# leddriverv3.net
KiCad netlist of a schematic drawn in EAGLE
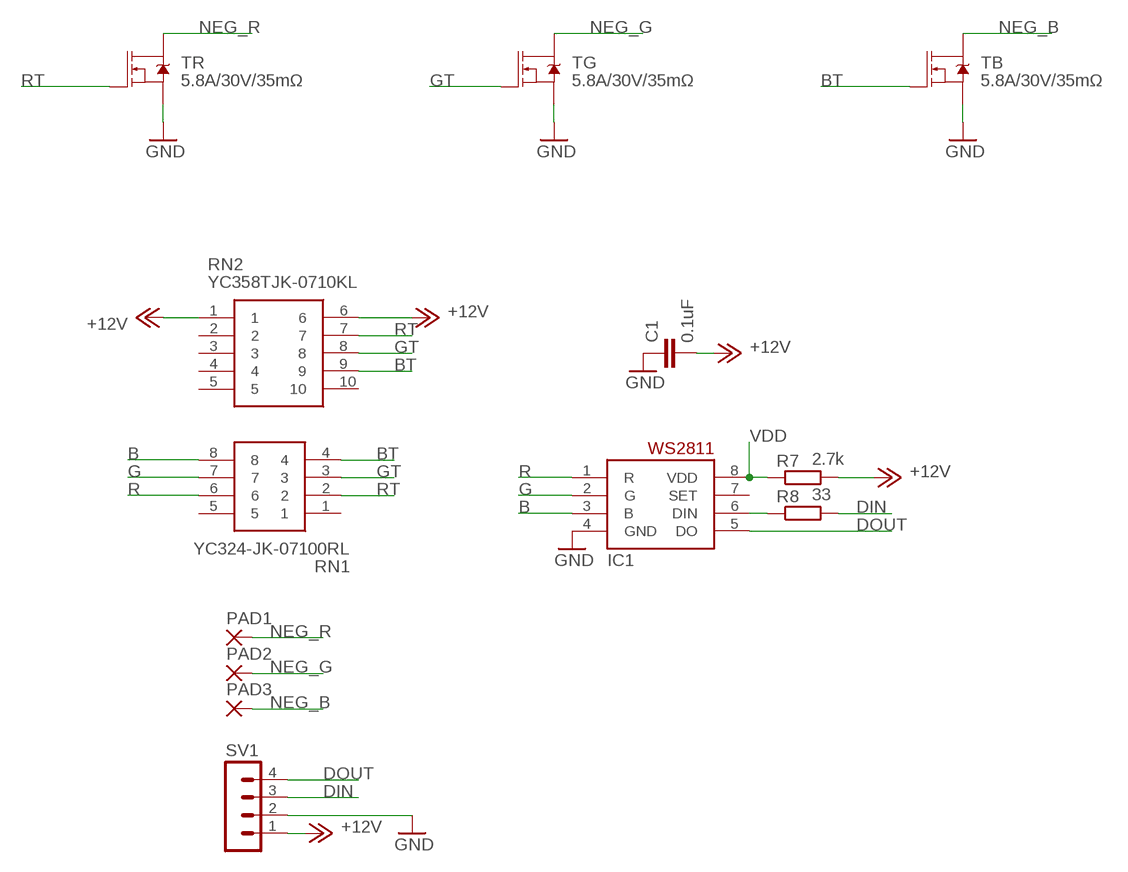
[diagram p0: schematic, sheet 1]

(export (version "E")
  (design (tool "Eeschema 10.0.6"))
  (components
    (comp (ref "C1")
      (value "0.1uF")
      (footprint "eagle-import:C1206")
      (libsource (lib "eagle-import") (part "C-EUC1206"))
    )
    (comp (ref "IC1")
      (value "WS2811-SOP8")
      (footprint "eagle-import:SO08-SKINNYPADS")
      (libsource (lib "eagle-import") (part "WS2811-SOP8"))
    )
    (comp (ref "PAD1")
      (value "3,81/1,4")
      (footprint "eagle-import:3,81_1,4")
      (libsource (lib "eagle-import") (part "3,81/1,4"))
    )
    (comp (ref "PAD2")
      (value "3,81/1,4")
      (footprint "eagle-import:3,81_1,4")
      (libsource (lib "eagle-import") (part "3,81/1,4"))
    )
    (comp (ref "PAD3")
      (value "3,81/1,4")
      (footprint "eagle-import:3,81_1,4")
      (libsource (lib "eagle-import") (part "3,81/1,4"))
    )
    (comp (ref "R7")
      (value "2.7k")
      (footprint "eagle-import:R0805")
      (libsource (lib "eagle-import") (part "R-EU_R0805"))
    )
    (comp (ref "R8")
      (value "33")
      (footprint "eagle-import:R0805")
      (libsource (lib "eagle-import") (part "R-EU_R0805"))
    )
    (comp (ref "RN1")
      (value "YC324-JK-07100RL")
      (footprint "eagle-import:YC324JK07100RL")
      (fields (field (name "MOUSER_PART_NUMBER") "603-YC324-JK-07100RL"))
      (libsource (lib "eagle-import") (part "YC324-JK-07100RL"))
    )
    (comp (ref "RN2")
      (value "YC358TJK-0710KL")
      (footprint "eagle-import:YC358T")
      (fields (field (name "MOUSER_PART_NUMBER") "603-YC358TJK-0710KL"))
      (libsource (lib "eagle-import") (part "YC358TJK-0710KL"))
    )
    (comp (ref "SV1")
      (value "MA04-1")
      (footprint "eagle-import:MA04-1")
      (libsource (lib "eagle-import") (part "MA04-1"))
    )
    (comp (ref "TB")
      (value "5.8A/30V/35mΩ")
      (footprint "eagle-import:SOT23-3")
      (libsource (lib "eagle-import") (part "MOSFET-NCH-AO3404A"))
    )
    (comp (ref "TG")
      (value "5.8A/30V/35mΩ")
      (footprint "eagle-import:SOT23-3")
      (libsource (lib "eagle-import") (part "MOSFET-NCH-AO3404A"))
    )
    (comp (ref "TR")
      (value "5.8A/30V/35mΩ")
      (footprint "eagle-import:SOT23-3")
      (libsource (lib "eagle-import") (part "MOSFET-NCH-AO3404A"))
    )
  )
  (nets
    (net (code "1") (name "+12V") (class "Default")
      (node (ref "C1") (pin "2") (pinfunction "2_2") (pintype "passive"))
      (node (ref "R7") (pin "2") (pinfunction "2_2") (pintype "passive"))
      (node (ref "RN2") (pin "1") (pinfunction "1_1") (pintype "bidirectional"))
      (node (ref "RN2") (pin "6") (pinfunction "6_6") (pintype "bidirectional"))
      (node (ref "SV1") (pin "1") (pinfunction "1_1") (pintype "passive"))
    )
    (net (code "2") (name "/B") (class "Default")
      (node (ref "IC1") (pin "3") (pinfunction "B_3") (pintype "open_collector"))
      (node (ref "RN1") (pin "8") (pinfunction "8_8") (pintype "bidirectional"))
    )
    (net (code "3") (name "/BT") (class "Default")
      (node (ref "RN1") (pin "4") (pinfunction "4_4") (pintype "bidirectional"))
      (node (ref "RN2") (pin "9") (pinfunction "9_9") (pintype "bidirectional"))
      (node (ref "TB") (pin "1") (pinfunction "G_1") (pintype "bidirectional"))
    )
    (net (code "4") (name "/DIN") (class "Default")
      (node (ref "R8") (pin "2") (pinfunction "2_2") (pintype "passive"))
      (node (ref "SV1") (pin "3") (pinfunction "3_3") (pintype "passive"))
    )
    (net (code "5") (name "/DOUT") (class "Default")
      (node (ref "IC1") (pin "5") (pinfunction "DO_5") (pintype "output"))
      (node (ref "SV1") (pin "4") (pinfunction "4_4") (pintype "passive"))
    )
    (net (code "6") (name "/G") (class "Default")
      (node (ref "IC1") (pin "2") (pinfunction "G_2") (pintype "open_collector"))
      (node (ref "RN1") (pin "7") (pinfunction "7_7") (pintype "bidirectional"))
    )
    (net (code "7") (name "/GT") (class "Default")
      (node (ref "RN1") (pin "3") (pinfunction "3_3") (pintype "bidirectional"))
      (node (ref "RN2") (pin "8") (pinfunction "8_8") (pintype "bidirectional"))
      (node (ref "TG") (pin "1") (pinfunction "G_1") (pintype "bidirectional"))
    )
    (net (code "8") (name "/NEG_B") (class "Default")
      (node (ref "PAD3") (pin "1") (pinfunction "P_1") (pintype "passive"))
      (node (ref "TB") (pin "3") (pinfunction "D_3") (pintype "bidirectional"))
    )
    (net (code "9") (name "/NEG_G") (class "Default")
      (node (ref "PAD2") (pin "1") (pinfunction "P_1") (pintype "passive"))
      (node (ref "TG") (pin "3") (pinfunction "D_3") (pintype "bidirectional"))
    )
    (net (code "10") (name "/NEG_R") (class "Default")
      (node (ref "PAD1") (pin "1") (pinfunction "P_1") (pintype "passive"))
      (node (ref "TR") (pin "3") (pinfunction "D_3") (pintype "bidirectional"))
    )
    (net (code "11") (name "/R") (class "Default")
      (node (ref "IC1") (pin "1") (pinfunction "R_1") (pintype "open_collector"))
      (node (ref "RN1") (pin "6") (pinfunction "6_6") (pintype "bidirectional"))
    )
    (net (code "12") (name "/RT") (class "Default")
      (node (ref "RN1") (pin "2") (pinfunction "2_2") (pintype "bidirectional"))
      (node (ref "RN2") (pin "7") (pinfunction "7_7") (pintype "bidirectional"))
      (node (ref "TR") (pin "1") (pinfunction "G_1") (pintype "bidirectional"))
    )
    (net (code "13") (name "/VDD") (class "Default")
      (node (ref "IC1") (pin "8") (pinfunction "VDD_8") (pintype "power_in"))
      (node (ref "R7") (pin "1") (pinfunction "1_1") (pintype "passive"))
    )
    (net (code "14") (name "GND") (class "Default")
      (node (ref "C1") (pin "1") (pinfunction "1_1") (pintype "passive"))
      (node (ref "IC1") (pin "4") (pinfunction "GND_4") (pintype "power_in"))
      (node (ref "SV1") (pin "2") (pinfunction "2_2") (pintype "passive"))
      (node (ref "TB") (pin "2") (pinfunction "S_2") (pintype "bidirectional"))
      (node (ref "TG") (pin "2") (pinfunction "S_2") (pintype "bidirectional"))
      (node (ref "TR") (pin "2") (pinfunction "S_2") (pintype "bidirectional"))
    )
    (net (code "15") (name "Net-(IC1-DIN)") (class "Default")
      (node (ref "IC1") (pin "6") (pinfunction "DIN_6") (pintype "input"))
      (node (ref "R8") (pin "1") (pinfunction "1_1") (pintype "passive"))
    )
    (net (code "16") (name "unconnected-(IC1-SET-Pad7)") (class "Default")
      (node (ref "IC1") (pin "7") (pinfunction "SET_7") (pintype "input"))
    )
    (net (code "17") (name "unconnected-(RN1-Pad1)") (class "Default")
      (node (ref "RN1") (pin "1") (pinfunction "1_1") (pintype "bidirectional"))
    )
    (net (code "18") (name "unconnected-(RN1-Pad5)") (class "Default")
      (node (ref "RN1") (pin "5") (pinfunction "5_5") (pintype "bidirectional"))
    )
    (net (code "19") (name "unconnected-(RN2-Pad2)") (class "Default")
      (node (ref "RN2") (pin "2") (pinfunction "2_2") (pintype "bidirectional"))
    )
    (net (code "20") (name "unconnected-(RN2-Pad3)") (class "Default")
      (node (ref "RN2") (pin "3") (pinfunction "3_3") (pintype "bidirectional"))
    )
    (net (code "21") (name "unconnected-(RN2-Pad4)") (class "Default")
      (node (ref "RN2") (pin "4") (pinfunction "4_4") (pintype "bidirectional"))
    )
    (net (code "22") (name "unconnected-(RN2-Pad5)") (class "Default")
      (node (ref "RN2") (pin "5") (pinfunction "5_5") (pintype "bidirectional"))
    )
    (net (code "23") (name "unconnected-(RN2-Pad10)") (class "Default")
      (node (ref "RN2") (pin "10") (pinfunction "10_10") (pintype "bidirectional"))
    )
  )
)
